# UCENGSOC_BadgeCore.net
KiCad netlist of a schematic drawn in EAGLE
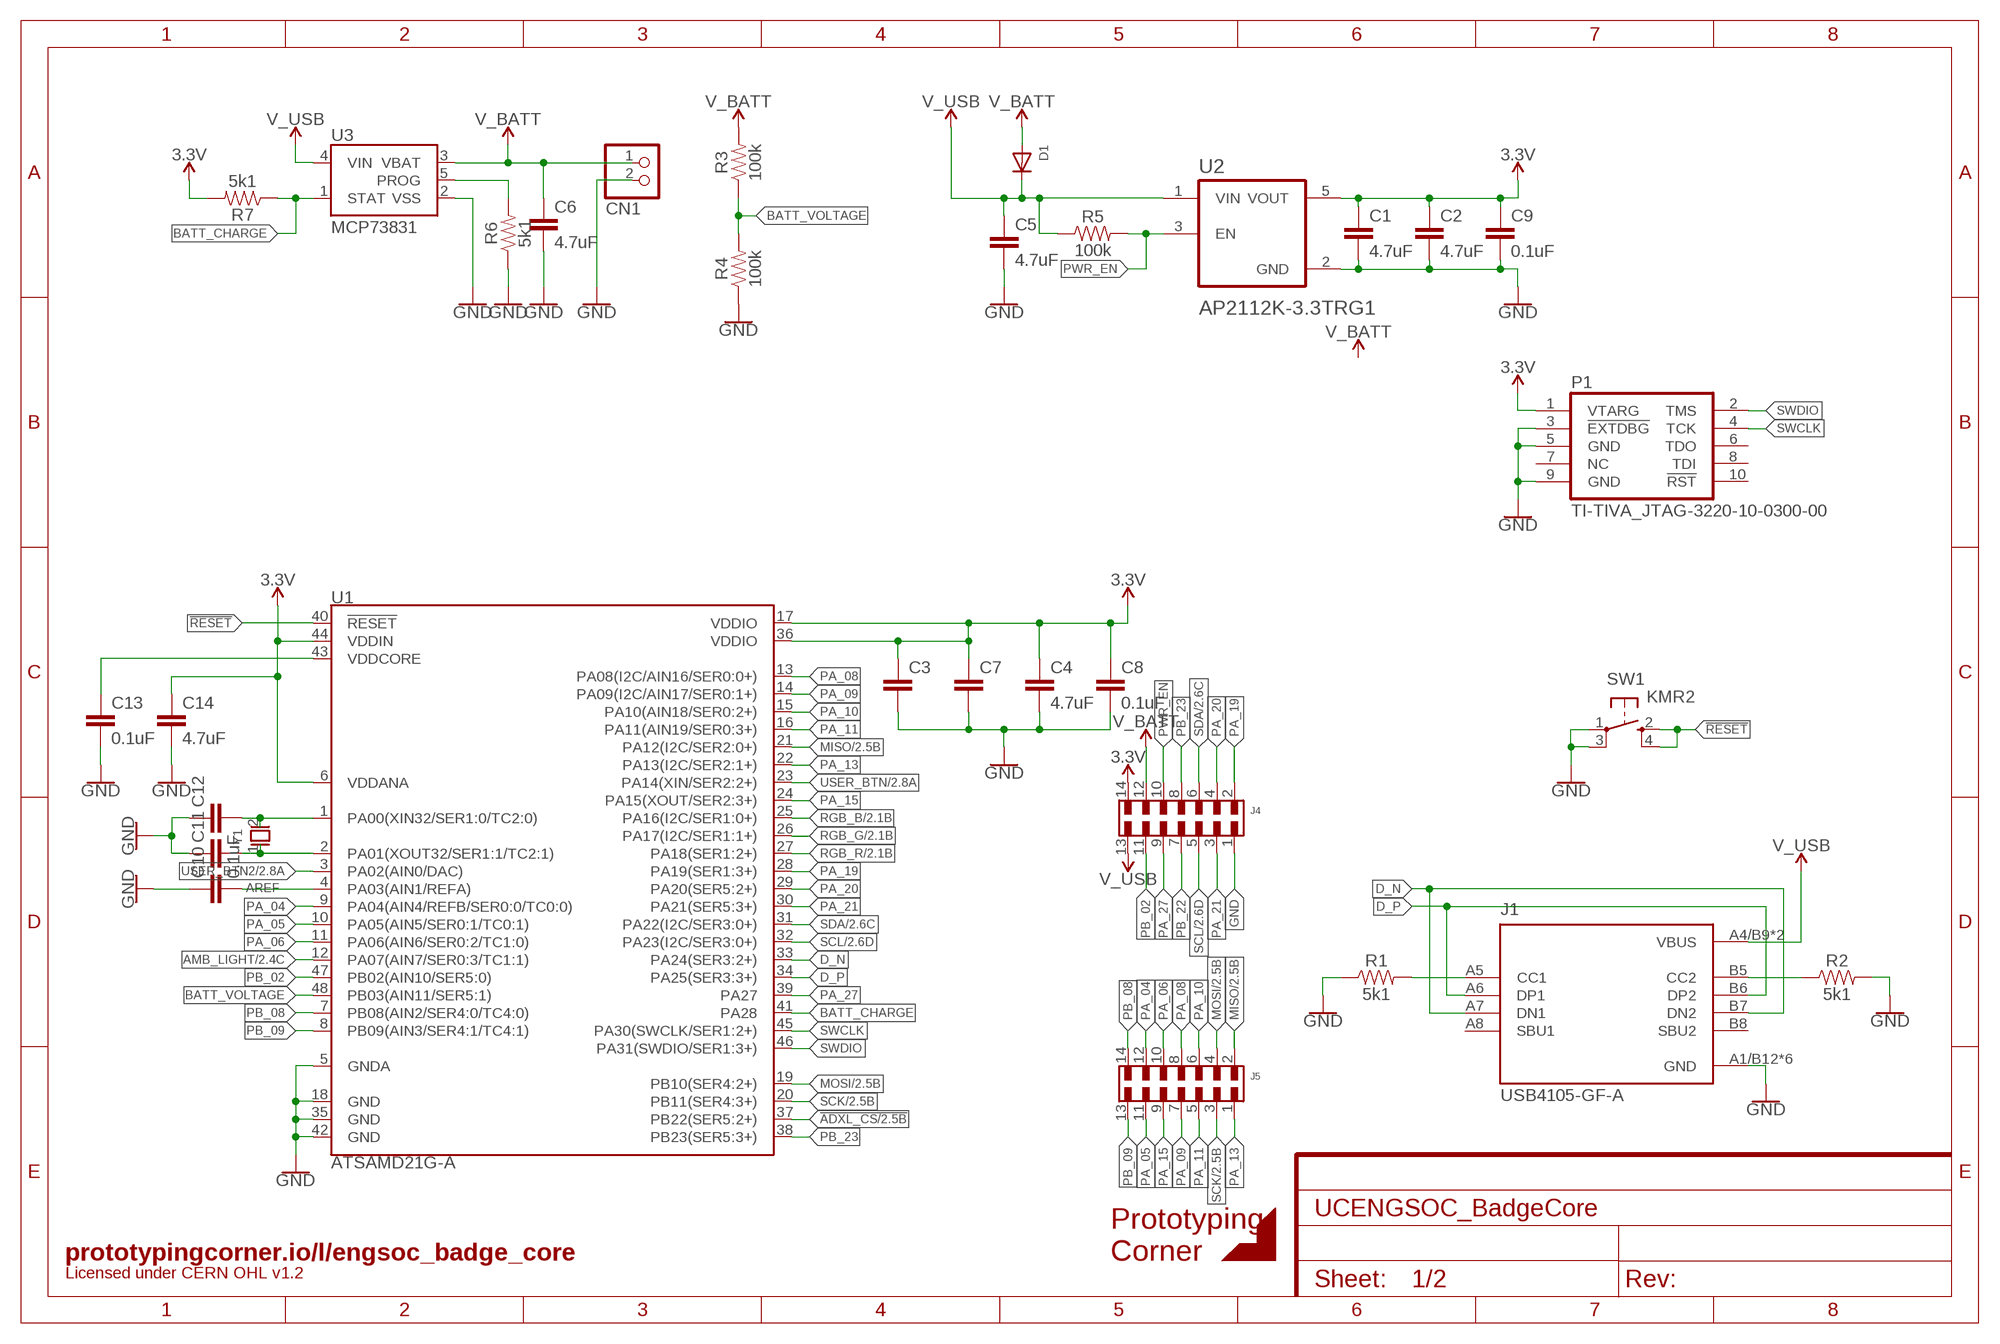
[diagram p0: schematic, sheet 1]
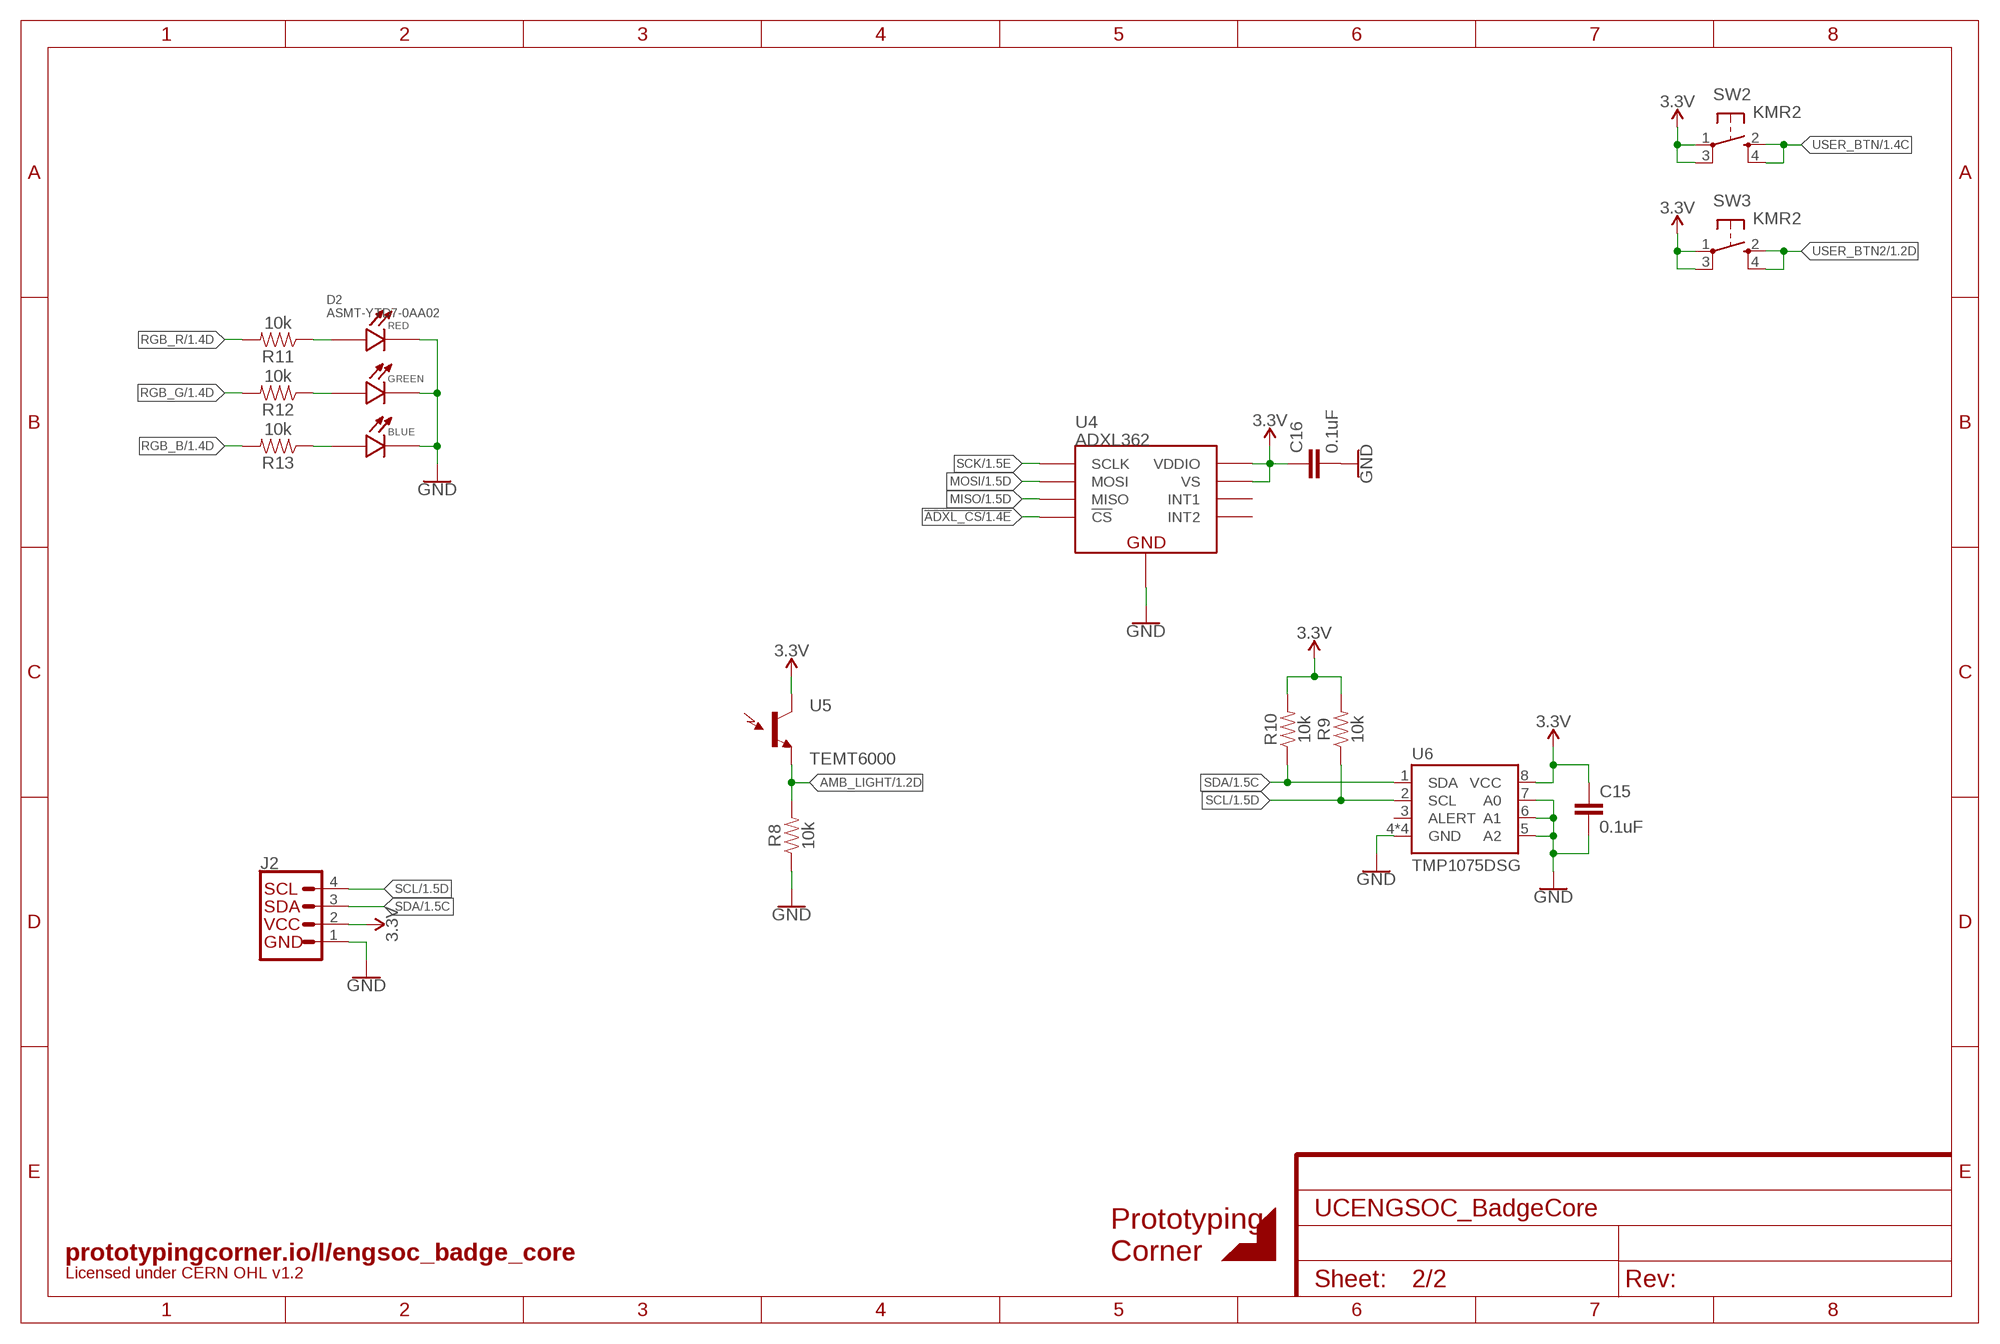
[diagram p1: schematic, sheet 2]

(export (version "E")
  (design (tool "Eeschema 10.0.6"))
  (components
    (comp (ref "C1")
      (value "4.7uF")
      (footprint "eagle-import:1206")
      (libsource (lib "eagle-import") (part "4.7UF-1206-16V-(+80/-20%)"))
    )
    (comp (ref "C2")
      (value "4.7uF")
      (footprint "eagle-import:1206")
      (libsource (lib "eagle-import") (part "4.7UF-1206-16V-(+80/-20%)"))
    )
    (comp (ref "C3")
      (value "4.7UF-1206-16V-(+80/-20%)")
      (footprint "eagle-import:1206")
      (libsource (lib "eagle-import") (part "4.7UF-1206-16V-(+80/-20%)"))
    )
    (comp (ref "C4")
      (value "4.7uF")
      (footprint "eagle-import:1206")
      (libsource (lib "eagle-import") (part "4.7UF-1206-16V-(+80/-20%)"))
    )
    (comp (ref "C5")
      (value "4.7uF")
      (footprint "eagle-import:1206")
      (libsource (lib "eagle-import") (part "4.7UF-1206-16V-(+80/-20%)"))
    )
    (comp (ref "C6")
      (value "4.7uF")
      (footprint "eagle-import:1206")
      (libsource (lib "eagle-import") (part "4.7UF-1206-16V-(+80/-20%)"))
    )
    (comp (ref "C7")
      (value "0.1UF-0603-25V-5%")
      (footprint "eagle-import:0603")
      (libsource (lib "eagle-import") (part "SparkFun-Capacitors_510_0.1UF-0603-25V-5%"))
    )
    (comp (ref "C8")
      (value "0.1uF")
      (footprint "eagle-import:0603")
      (libsource (lib "eagle-import") (part "SparkFun-Capacitors_510_0.1UF-0603-25V-5%"))
    )
    (comp (ref "C9")
      (value "0.1uF")
      (footprint "eagle-import:0603")
      (libsource (lib "eagle-import") (part "SparkFun-Capacitors_510_0.1UF-0603-25V-5%"))
    )
    (comp (ref "C10")
      (value "0.1uF")
      (footprint "eagle-import:0603")
      (libsource (lib "eagle-import") (part "SparkFun-Capacitors_510_0.1UF-0603-25V-5%"))
    )
    (comp (ref "C11")
      (value "15PF-0603-50V-5%")
      (footprint "eagle-import:0603")
      (libsource (lib "eagle-import") (part "15PF-0603-50V-5%"))
    )
    (comp (ref "C12")
      (value "15PF-0603-50V-5%")
      (footprint "eagle-import:0603")
      (libsource (lib "eagle-import") (part "15PF-0603-50V-5%"))
    )
    (comp (ref "C13")
      (value "0.1uF")
      (footprint "eagle-import:0603")
      (libsource (lib "eagle-import") (part "SparkFun-Capacitors_510_0.1UF-0603-25V-5%"))
    )
    (comp (ref "C14")
      (value "4.7uF")
      (footprint "eagle-import:1206")
      (libsource (lib "eagle-import") (part "4.7UF-1206-16V-(+80/-20%)"))
    )
    (comp (ref "CN1")
      (value "JST_2PIN-SMT-RA")
      (footprint "eagle-import:JST-PH-2-SMT-RA")
      (libsource (lib "eagle-import") (part "JST_2PIN-SMT-RA"))
    )
    (comp (ref "D1")
      (value "DIODE_SOD-123FL")
      (footprint "eagle-import:SOD-123FL")
      (libsource (lib "eagle-import") (part "DIODE_SOD-123FL"))
    )
    (comp (ref "J1")
      (value "USB4105-GF-A")
      (footprint "eagle-import:GCT_USB4105-GF-A")
      (fields (field (name "MF") "GCT"))
      (libsource (lib "eagle-import") (part "USB4105-GF-A"))
    )
    (comp (ref "J4")
      (value "6100XX21121_61001421121")
      (footprint "eagle-import:61001421121")
      (libsource (lib "eagle-import") (part "6100XX21121_61001421121"))
    )
    (comp (ref "J5")
      (value "6100XX21121_61001421121")
      (footprint "eagle-import:61001421121")
      (libsource (lib "eagle-import") (part "6100XX21121_61001421121"))
    )
    (comp (ref "P1")
      (value "TI-TIVA_JTAG-3220-10-0300-00")
      (footprint "eagle-import:TI-TIVA_3220-10-0300-00")
      (libsource (lib "eagle-import") (part "TI-TIVA_JTAG-3220-10-0300-00"))
    )
    (comp (ref "R1")
      (value "5k1")
      (footprint "eagle-import:0603")
      (libsource (lib "eagle-import") (part "RESISTOR0603"))
    )
    (comp (ref "R2")
      (value "5k1")
      (footprint "eagle-import:0603")
      (libsource (lib "eagle-import") (part "RESISTOR0603"))
    )
    (comp (ref "R3")
      (value "100k")
      (footprint "eagle-import:0603")
      (libsource (lib "eagle-import") (part "RESISTOR0603"))
    )
    (comp (ref "R4")
      (value "100k")
      (footprint "eagle-import:0603")
      (libsource (lib "eagle-import") (part "RESISTOR0603"))
    )
    (comp (ref "R5")
      (value "100k")
      (footprint "eagle-import:0603")
      (libsource (lib "eagle-import") (part "RESISTOR0603"))
    )
    (comp (ref "R6")
      (value "5k1")
      (footprint "eagle-import:0603")
      (libsource (lib "eagle-import") (part "RESISTOR0603"))
    )
    (comp (ref "R7")
      (value "5k1")
      (footprint "eagle-import:0603")
      (libsource (lib "eagle-import") (part "RESISTOR0603"))
    )
    (comp (ref "SW1")
      (value "KMR2")
      (footprint "eagle-import:KMR2")
      (libsource (lib "eagle-import") (part "SPST_TACT-KMR2"))
    )
    (comp (ref "U$1")
      (value "LOGOSMALL_COPPER")
      (footprint "eagle-import:LOGO_SMALL_COPPER")
      (libsource (lib "eagle-import") (part "LOGOSMALL_COPPER"))
    )
    (comp (ref "U1")
      (value "ATSAMD21G-A")
      (footprint "eagle-import:TQFP-48")
      (libsource (lib "eagle-import") (part "ATSAMD21G-A"))
    )
    (comp (ref "U2")
      (value "AP2112K-3.3TRG1")
      (footprint "eagle-import:SOT95P285X140-5N")
      (fields
        (field (name "DIGI-KEY_PART_NUMBER") "AP2112K-3.3TRG1DICT-ND")
        (field (name "MF") "Diodes Inc.")
      )
      (libsource (lib "eagle-import") (part "AP2112K-3.3TRG1"))
    )
    (comp (ref "U3")
      (value "MCP73831")
      (footprint "eagle-import:SOT23-5")
      (libsource (lib "eagle-import") (part "MCP73831"))
    )
    (comp (ref "Y1")
      (value "FC-135_32.7680KA-A0")
      (footprint "eagle-import:XTAL_FC-135_32.7680KA-A0")
      (fields
        (field (name "DIGI-KEY_PART_NUMBER") "SER4077CT-ND")
        (field (name "MF") "EPSON")
        (field (name "MP") "FC-135 32.7680KA-A0")
      )
      (libsource (lib "eagle-import") (part "FC-135_32.7680KA-A0"))
    )
    (comp (ref "C15")
      (value "0.1uF")
      (footprint "eagle-import:0603")
      (libsource (lib "eagle-import") (part "0.1UF-0603-25V-(+80/-20%)"))
    )
    (comp (ref "C16")
      (value "0.1uF")
      (footprint "eagle-import:0603")
      (libsource (lib "eagle-import") (part "0.1UF-0603-25V-(+80/-20%)"))
    )
    (comp (ref "D2")
      (value "ASMT-YTD7-0AA02")
      (footprint "eagle-import:LED_ASMT-YTD7-0AA02")
      (fields (field (name "MF") "Broadcom Limited"))
      (libsource (lib "eagle-import") (part "ASMT-YTD7-0AA02"))
    )
    (comp (ref "J2")
      (value "QWIIC_CONNECTORJS-1MM")
      (footprint "eagle-import:1X04_1MM_RA")
      (libsource (lib "eagle-import") (part "QWIIC_CONNECTORJS-1MM"))
    )
    (comp (ref "R8")
      (value "10k")
      (footprint "eagle-import:0603")
      (libsource (lib "eagle-import") (part "10KOHM-0603-1/10W-1%"))
    )
    (comp (ref "R9")
      (value "10k")
      (footprint "eagle-import:0603")
      (libsource (lib "eagle-import") (part "10KOHM-0603-1/10W-1%"))
    )
    (comp (ref "R10")
      (value "10k")
      (footprint "eagle-import:0603")
      (libsource (lib "eagle-import") (part "10KOHM-0603-1/10W-1%"))
    )
    (comp (ref "R11")
      (value "10k")
      (footprint "eagle-import:0603")
      (libsource (lib "eagle-import") (part "10KOHM-0603-1/10W-1%"))
    )
    (comp (ref "R12")
      (value "10k")
      (footprint "eagle-import:0603")
      (libsource (lib "eagle-import") (part "10KOHM-0603-1/10W-1%"))
    )
    (comp (ref "R13")
      (value "10k")
      (footprint "eagle-import:0603")
      (libsource (lib "eagle-import") (part "10KOHM-0603-1/10W-1%"))
    )
    (comp (ref "SW2")
      (value "KMR2")
      (footprint "eagle-import:KMR2")
      (libsource (lib "eagle-import") (part "SPST_TACT-KMR2"))
    )
    (comp (ref "SW3")
      (value "KMR2")
      (footprint "eagle-import:KMR2")
      (libsource (lib "eagle-import") (part "SPST_TACT-KMR2"))
    )
    (comp (ref "U$2")
      (value "LOGOSMALL_COPPER")
      (footprint "eagle-import:LOGO_SMALL_COPPER")
      (libsource (lib "eagle-import") (part "LOGOSMALL_COPPER"))
    )
    (comp (ref "U4")
      (value "ADXL362")
      (footprint "eagle-import:ADXL362")
      (libsource (lib "eagle-import") (part "ADXL362"))
    )
    (comp (ref "U5")
      (value "TEMT6000")
      (footprint "eagle-import:TEMT6000-SEN")
      (libsource (lib "eagle-import") (part "TEMT6000"))
    )
    (comp (ref "U6")
      (value "TMP1075DSG")
      (footprint "eagle-import:WSON8")
      (libsource (lib "eagle-import") (part "TMP1075DSG"))
    )
  )
  (nets
    (net (code "1") (name "3.3V") (class "Default")
      (node (ref "C1") (pin "1") (pinfunction "1_1") (pintype "passive"))
      (node (ref "C14") (pin "1") (pinfunction "1_1") (pintype "passive"))
      (node (ref "C15") (pin "1") (pinfunction "1_1") (pintype "passive"))
      (node (ref "C16") (pin "1") (pinfunction "1_1") (pintype "passive"))
      (node (ref "C2") (pin "1") (pinfunction "1_1") (pintype "passive"))
      (node (ref "C3") (pin "1") (pinfunction "1_1") (pintype "passive"))
      (node (ref "C4") (pin "1") (pinfunction "1_1") (pintype "passive"))
      (node (ref "C7") (pin "1") (pinfunction "1_1") (pintype "passive"))
      (node (ref "C8") (pin "1") (pinfunction "1_1") (pintype "passive"))
      (node (ref "C9") (pin "1") (pinfunction "1_1") (pintype "passive"))
      (node (ref "J2") (pin "2") (pinfunction "VCC_2") (pintype "power_in"))
      (node (ref "J4") (pin "14") (pinfunction "14_14") (pintype "passive"))
      (node (ref "P1") (pin "1") (pinfunction "VTARG_1") (pintype "bidirectional"))
      (node (ref "R10") (pin "2") (pinfunction "2_2") (pintype "passive"))
      (node (ref "R7") (pin "2") (pinfunction "2_2") (pintype "passive"))
      (node (ref "R9") (pin "2") (pinfunction "2_2") (pintype "passive"))
      (node (ref "SW2") (pin "1") (pinfunction "P_1") (pintype "passive"))
      (node (ref "SW2") (pin "3") (pinfunction "P1_3") (pintype "passive"))
      (node (ref "SW3") (pin "1") (pinfunction "P_1") (pintype "passive"))
      (node (ref "SW3") (pin "3") (pinfunction "P1_3") (pintype "passive"))
      (node (ref "U1") (pin "17") (pinfunction "VDDIO_17") (pintype "bidirectional"))
      (node (ref "U1") (pin "36") (pinfunction "VDDIO_36") (pintype "bidirectional"))
      (node (ref "U1") (pin "44") (pinfunction "VDDIN_44") (pintype "bidirectional"))
      (node (ref "U1") (pin "6") (pinfunction "VDDANA_6") (pintype "bidirectional"))
      (node (ref "U2") (pin "5") (pinfunction "VOUT_5") (pintype "power_in"))
      (node (ref "U4") (pin "P$1") (pinfunction "VDDIO_P$1") (pintype "bidirectional"))
      (node (ref "U4") (pin "P$14") (pinfunction "VS_P$14") (pintype "bidirectional"))
      (node (ref "U5") (pin "COLLECTOR") (pinfunction "C1_COLLECTOR") (pintype "passive"))
      (node (ref "U6") (pin "8") (pinfunction "VCC_8") (pintype "bidirectional"))
    )
    (net (code "2") (name "AMB_LIGHT") (class "Default")
      (node (ref "R8") (pin "2") (pinfunction "2_2") (pintype "passive"))
      (node (ref "U1") (pin "12") (pinfunction "PA07(AIN7/SER0:3/TC1:1)_12") (pintype "bidirectional"))
      (node (ref "U5") (pin "EMITTER") (pinfunction "E1_EMITTER") (pintype "passive"))
    )
    (net (code "3") (name "AREF") (class "Default")
      (node (ref "C10") (pin "2") (pinfunction "2_2") (pintype "passive"))
      (node (ref "U1") (pin "4") (pinfunction "PA03(AIN1/REFA)_4") (pintype "bidirectional"))
    )
    (net (code "4") (name "BATT_CHARGE") (class "Default")
      (node (ref "R7") (pin "1") (pinfunction "1_1") (pintype "passive"))
      (node (ref "U1") (pin "41") (pinfunction "PA28_41") (pintype "bidirectional"))
      (node (ref "U3") (pin "1") (pinfunction "STAT_1") (pintype "output"))
    )
    (net (code "5") (name "BATT_VOLTAGE") (class "Default")
      (node (ref "R3") (pin "1") (pinfunction "1_1") (pintype "passive"))
      (node (ref "R4") (pin "2") (pinfunction "2_2") (pintype "passive"))
      (node (ref "U1") (pin "48") (pinfunction "PB03(AIN11/SER5:1)_48") (pintype "bidirectional"))
    )
    (net (code "6") (name "D_N") (class "Default")
      (node (ref "J1") (pin "A7") (pinfunction "DN1_A7") (pintype "bidirectional"))
      (node (ref "J1") (pin "B7") (pinfunction "DN2_B7") (pintype "bidirectional"))
      (node (ref "U1") (pin "33") (pinfunction "PA24(SER3:2+)_33") (pintype "bidirectional"))
    )
    (net (code "7") (name "D_P") (class "Default")
      (node (ref "J1") (pin "A6") (pinfunction "DP1_A6") (pintype "bidirectional"))
      (node (ref "J1") (pin "B6") (pinfunction "DP2_B6") (pintype "bidirectional"))
      (node (ref "U1") (pin "34") (pinfunction "PA25(SER3:3+)_34") (pintype "bidirectional"))
    )
    (net (code "8") (name "GND") (class "Default")
      (node (ref "C1") (pin "2") (pinfunction "2_2") (pintype "passive"))
      (node (ref "C10") (pin "1") (pinfunction "1_1") (pintype "passive"))
      (node (ref "C11") (pin "1") (pinfunction "1_1") (pintype "passive"))
      (node (ref "C12") (pin "1") (pinfunction "1_1") (pintype "passive"))
      (node (ref "C13") (pin "2") (pinfunction "2_2") (pintype "passive"))
      (node (ref "C14") (pin "2") (pinfunction "2_2") (pintype "passive"))
      (node (ref "C15") (pin "2") (pinfunction "2_2") (pintype "passive"))
      (node (ref "C16") (pin "2") (pinfunction "2_2") (pintype "passive"))
      (node (ref "C2") (pin "2") (pinfunction "2_2") (pintype "passive"))
      (node (ref "C3") (pin "2") (pinfunction "2_2") (pintype "passive"))
      (node (ref "C4") (pin "2") (pinfunction "2_2") (pintype "passive"))
      (node (ref "C5") (pin "2") (pinfunction "2_2") (pintype "passive"))
      (node (ref "C6") (pin "2") (pinfunction "2_2") (pintype "passive"))
      (node (ref "C7") (pin "2") (pinfunction "2_2") (pintype "passive"))
      (node (ref "C8") (pin "2") (pinfunction "2_2") (pintype "passive"))
      (node (ref "C9") (pin "2") (pinfunction "2_2") (pintype "passive"))
      (node (ref "CN1") (pin "2") (pinfunction "1_2") (pintype "passive"))
      (node (ref "D2") (pin "1") (pinfunction "B_C_1") (pintype "passive"))
      (node (ref "D2") (pin "2") (pinfunction "G_C_2") (pintype "passive"))
      (node (ref "D2") (pin "3") (pinfunction "R_C_3") (pintype "passive"))
      (node (ref "J1") (pin "A1/B12") (pinfunction "GND_A1/B12") (pintype "power_in"))
      (node (ref "J1") (pin "B1/A12") (pinfunction "GND_B1/A12") (pintype "power_in"))
      (node (ref "J1") (pin "G1") (pinfunction "GND_G1") (pintype "power_in"))
      (node (ref "J1") (pin "G2") (pinfunction "GND_G2") (pintype "power_in"))
      (node (ref "J1") (pin "G3") (pinfunction "GND_G3") (pintype "power_in"))
      (node (ref "J1") (pin "G4") (pinfunction "GND_G4") (pintype "power_in"))
      (node (ref "J2") (pin "1") (pinfunction "GND_1") (pintype "power_in"))
      (node (ref "J4") (pin "1") (pinfunction "1_1") (pintype "passive"))
      (node (ref "P1") (pin "3") (pinfunction "~{EXTDBG}_3") (pintype "bidirectional"))
      (node (ref "P1") (pin "5") (pinfunction "GND_5") (pintype "bidirectional"))
      (node (ref "P1") (pin "9") (pinfunction "GND_9") (pintype "bidirectional"))
      (node (ref "R1") (pin "1") (pinfunction "1_1") (pintype "passive"))
      (node (ref "R2") (pin "2") (pinfunction "2_2") (pintype "passive"))
      (node (ref "R4") (pin "1") (pinfunction "1_1") (pintype "passive"))
      (node (ref "R6") (pin "1") (pinfunction "1_1") (pintype "passive"))
      (node (ref "R8") (pin "1") (pinfunction "1_1") (pintype "passive"))
      (node (ref "SW1") (pin "1") (pinfunction "P_1") (pintype "passive"))
      (node (ref "SW1") (pin "3") (pinfunction "P1_3") (pintype "passive"))
      (node (ref "U1") (pin "18") (pinfunction "GND_18") (pintype "bidirectional"))
      (node (ref "U1") (pin "35") (pinfunction "GND_35") (pintype "bidirectional"))
      (node (ref "U1") (pin "42") (pinfunction "GND_42") (pintype "bidirectional"))
      (node (ref "U1") (pin "5") (pinfunction "GNDA_5") (pintype "bidirectional"))
      (node (ref "U2") (pin "2") (pinfunction "GND_2") (pintype "power_in"))
      (node (ref "U3") (pin "2") (pinfunction "VSS_2") (pintype "power_in"))
      (node (ref "U4") (pin "P$12") (pinfunction "GND_P$12") (pintype "bidirectional"))
      (node (ref "U4") (pin "P$13") (pinfunction "GND_P$13") (pintype "bidirectional"))
      (node (ref "U4") (pin "P$16") (pinfunction "GND_P$16") (pintype "bidirectional"))
      (node (ref "U6") (pin "10") (pinfunction "GND_10") (pintype "bidirectional"))
      (node (ref "U6") (pin "11") (pinfunction "GND_11") (pintype "bidirectional"))
      (node (ref "U6") (pin "4") (pinfunction "GND_4") (pintype "bidirectional"))
      (node (ref "U6") (pin "5") (pinfunction "A2_5") (pintype "bidirectional"))
      (node (ref "U6") (pin "6") (pinfunction "A1_6") (pintype "bidirectional"))
      (node (ref "U6") (pin "7") (pinfunction "A0_7") (pintype "bidirectional"))
      (node (ref "U6") (pin "9") (pinfunction "GND_9") (pintype "bidirectional"))
    )
    (net (code "9") (name "MISO") (class "Default")
      (node (ref "J5") (pin "2") (pinfunction "2_2") (pintype "passive"))
      (node (ref "U1") (pin "21") (pinfunction "PA12(I2C/SER2:0+)_21") (pintype "bidirectional"))
      (node (ref "U4") (pin "P$7") (pinfunction "MISO_P$7") (pintype "bidirectional"))
    )
    (net (code "10") (name "MOSI") (class "Default")
      (node (ref "J5") (pin "4") (pinfunction "4_4") (pintype "passive"))
      (node (ref "U1") (pin "19") (pinfunction "PB10(SER4:2+)_19") (pintype "bidirectional"))
      (node (ref "U4") (pin "P$6") (pinfunction "MOSI_P$6") (pintype "bidirectional"))
    )
    (net (code "11") (name "Net-(D2-B_A)") (class "Default")
      (node (ref "D2") (pin "6") (pinfunction "B_A_6") (pintype "passive"))
      (node (ref "R13") (pin "1") (pinfunction "1_1") (pintype "passive"))
    )
    (net (code "12") (name "Net-(D2-G_A)") (class "Default")
      (node (ref "D2") (pin "5") (pinfunction "G_A_5") (pintype "passive"))
      (node (ref "R12") (pin "1") (pinfunction "1_1") (pintype "passive"))
    )
    (net (code "13") (name "Net-(D2-R_A)") (class "Default")
      (node (ref "D2") (pin "4") (pinfunction "R_A_4") (pintype "passive"))
      (node (ref "R11") (pin "1") (pinfunction "1_1") (pintype "passive"))
    )
    (net (code "14") (name "Net-(J1-CC1)") (class "Default")
      (node (ref "J1") (pin "A5") (pinfunction "CC1_A5") (pintype "bidirectional"))
      (node (ref "R1") (pin "2") (pinfunction "2_2") (pintype "passive"))
    )
    (net (code "15") (name "Net-(J1-CC2)") (class "Default")
      (node (ref "J1") (pin "B5") (pinfunction "CC2_B5") (pintype "bidirectional"))
      (node (ref "R2") (pin "1") (pinfunction "1_1") (pintype "passive"))
    )
    (net (code "16") (name "Net-(U1-PA00(XIN32{slash}SER1:0{slash}TC2:0))") (class "Default")
      (node (ref "C12") (pin "2") (pinfunction "2_2") (pintype "passive"))
      (node (ref "U1") (pin "1") (pinfunction "PA00(XIN32/SER1:0/TC2:0)_1") (pintype "bidirectional"))
      (node (ref "Y1") (pin "2") (pinfunction "2_2") (pintype "passive"))
    )
    (net (code "17") (name "Net-(U1-PA01(XOUT32{slash}SER1:1{slash}TC2:1))") (class "Default")
      (node (ref "C11") (pin "2") (pinfunction "2_2") (pintype "passive"))
      (node (ref "U1") (pin "2") (pinfunction "PA01(XOUT32/SER1:1/TC2:1)_2") (pintype "bidirectional"))
      (node (ref "Y1") (pin "1") (pinfunction "1_1") (pintype "passive"))
    )
    (net (code "18") (name "Net-(U1-VDDCORE)") (class "Default")
      (node (ref "C13") (pin "1") (pinfunction "1_1") (pintype "passive"))
      (node (ref "U1") (pin "43") (pinfunction "VDDCORE_43") (pintype "bidirectional"))
    )
    (net (code "19") (name "Net-(U3-PROG)") (class "Default")
      (node (ref "R6") (pin "2") (pinfunction "2_2") (pintype "passive"))
      (node (ref "U3") (pin "5") (pinfunction "PROG_5") (pintype "input"))
    )
    (net (code "20") (name "PA_04") (class "Default")
      (node (ref "J5") (pin "12") (pinfunction "12_12") (pintype "passive"))
      (node (ref "U1") (pin "9") (pinfunction "PA04(AIN4/REFB/SER0:0/TC0:0)_9") (pintype "bidirectional"))
    )
    (net (code "21") (name "PA_05") (class "Default")
      (node (ref "J5") (pin "11") (pinfunction "11_11") (pintype "passive"))
      (node (ref "U1") (pin "10") (pinfunction "PA05(AIN5/SER0:1/TC0:1)_10") (pintype "bidirectional"))
    )
    (net (code "22") (name "PA_06") (class "Default")
      (node (ref "J5") (pin "10") (pinfunction "10_10") (pintype "passive"))
      (node (ref "U1") (pin "11") (pinfunction "PA06(AIN6/SER0:2/TC1:0)_11") (pintype "bidirectional"))
    )
    (net (code "23") (name "PA_08") (class "Default")
      (node (ref "J5") (pin "8") (pinfunction "8_8") (pintype "passive"))
      (node (ref "U1") (pin "13") (pinfunction "PA08(I2C/AIN16/SER0:0+)_13") (pintype "bidirectional"))
    )
    (net (code "24") (name "PA_09") (class "Default")
      (node (ref "J5") (pin "7") (pinfunction "7_7") (pintype "passive"))
      (node (ref "U1") (pin "14") (pinfunction "PA09(I2C/AIN17/SER0:1+)_14") (pintype "bidirectional"))
    )
    (net (code "25") (name "PA_10") (class "Default")
      (node (ref "J5") (pin "6") (pinfunction "6_6") (pintype "passive"))
      (node (ref "U1") (pin "15") (pinfunction "PA10(AIN18/SER0:2+)_15") (pintype "bidirectional"))
    )
    (net (code "26") (name "PA_11") (class "Default")
      (node (ref "J5") (pin "5") (pinfunction "5_5") (pintype "passive"))
      (node (ref "U1") (pin "16") (pinfunction "PA11(AIN19/SER0:3+)_16") (pintype "bidirectional"))
    )
    (net (code "27") (name "PA_13") (class "Default")
      (node (ref "J5") (pin "1") (pinfunction "1_1") (pintype "passive"))
      (node (ref "U1") (pin "22") (pinfunction "PA13(I2C/SER2:1+)_22") (pintype "bidirectional"))
    )
    (net (code "28") (name "PA_15") (class "Default")
      (node (ref "J5") (pin "9") (pinfunction "9_9") (pintype "passive"))
      (node (ref "U1") (pin "24") (pinfunction "PA15(XOUT/SER2:3+)_24") (pintype "bidirectional"))
    )
    (net (code "29") (name "PA_19") (class "Default")
      (node (ref "J4") (pin "2") (pinfunction "2_2") (pintype "passive"))
      (node (ref "U1") (pin "28") (pinfunction "PA19(SER1:3+)_28") (pintype "bidirectional"))
    )
    (net (code "30") (name "PA_20") (class "Default")
      (node (ref "J4") (pin "4") (pinfunction "4_4") (pintype "passive"))
      (node (ref "U1") (pin "29") (pinfunction "PA20(SER5:2+)_29") (pintype "bidirectional"))
    )
    (net (code "31") (name "PA_21") (class "Default")
      (node (ref "J4") (pin "3") (pinfunction "3_3") (pintype "passive"))
      (node (ref "U1") (pin "30") (pinfunction "PA21(SER5:3+)_30") (pintype "bidirectional"))
    )
    (net (code "32") (name "PA_27") (class "Default")
      (node (ref "J4") (pin "9") (pinfunction "9_9") (pintype "passive"))
      (node (ref "U1") (pin "39") (pinfunction "PA27_39") (pintype "bidirectional"))
    )
    (net (code "33") (name "PB_02") (class "Default")
      (node (ref "J4") (pin "11") (pinfunction "11_11") (pintype "passive"))
      (node (ref "U1") (pin "47") (pinfunction "PB02(AIN10/SER5:0)_47") (pintype "bidirectional"))
    )
    (net (code "34") (name "PB_08") (class "Default")
      (node (ref "J5") (pin "14") (pinfunction "14_14") (pintype "passive"))
      (node (ref "U1") (pin "7") (pinfunction "PB08(AIN2/SER4:0/TC4:0)_7") (pintype "bidirectional"))
    )
    (net (code "35") (name "PB_09") (class "Default")
      (node (ref "J5") (pin "13") (pinfunction "13_13") (pintype "passive"))
      (node (ref "U1") (pin "8") (pinfunction "PB09(AIN3/SER4:1/TC4:1)_8") (pintype "bidirectional"))
    )
    (net (code "36") (name "PB_22") (class "Default")
      (node (ref "J4") (pin "7") (pinfunction "7_7") (pintype "passive"))
    )
    (net (code "37") (name "PB_23") (class "Default")
      (node (ref "J4") (pin "8") (pinfunction "8_8") (pintype "passive"))
      (node (ref "U1") (pin "38") (pinfunction "PB23(SER5:3+)_38") (pintype "bidirectional"))
    )
    (net (code "38") (name "PWR_EN") (class "Default")
      (node (ref "J4") (pin "10") (pinfunction "10_10") (pintype "passive"))
      (node (ref "R5") (pin "2") (pinfunction "2_2") (pintype "passive"))
      (node (ref "U2") (pin "3") (pinfunction "EN_3") (pintype "input"))
    )
    (net (code "39") (name "RGB_B") (class "Default")
      (node (ref "R13") (pin "2") (pinfunction "2_2") (pintype "passive"))
      (node (ref "U1") (pin "25") (pinfunction "PA16(I2C/SER1:0+)_25") (pintype "bidirectional"))
    )
    (net (code "40") (name "RGB_G") (class "Default")
      (node (ref "R12") (pin "2") (pinfunction "2_2") (pintype "passive"))
      (node (ref "U1") (pin "26") (pinfunction "PA17(I2C/SER1:1+)_26") (pintype "bidirectional"))
    )
    (net (code "41") (name "RGB_R") (class "Default")
      (node (ref "R11") (pin "2") (pinfunction "2_2") (pintype "passive"))
      (node (ref "U1") (pin "27") (pinfunction "PA18(SER1:2+)_27") (pintype "bidirectional"))
    )
    (net (code "42") (name "SCK") (class "Default")
      (node (ref "J5") (pin "3") (pinfunction "3_3") (pintype "passive"))
      (node (ref "U1") (pin "20") (pinfunction "PB11(SER4:3+)_20") (pintype "bidirectional"))
      (node (ref "U4") (pin "P$4") (pinfunction "SCLK_P$4") (pintype "bidirectional"))
    )
    (net (code "43") (name "SCL") (class "Default")
      (node (ref "J2") (pin "4") (pinfunction "SCL_4") (pintype "passive"))
      (node (ref "J4") (pin "5") (pinfunction "5_5") (pintype "passive"))
      (node (ref "R9") (pin "1") (pinfunction "1_1") (pintype "passive"))
      (node (ref "U1") (pin "32") (pinfunction "PA23(I2C/SER3:0+)_32") (pintype "bidirectional"))
      (node (ref "U6") (pin "2") (pinfunction "SCL_2") (pintype "bidirectional"))
    )
    (net (code "44") (name "SDA") (class "Default")
      (node (ref "J2") (pin "3") (pinfunction "SDA_3") (pintype "passive"))
      (node (ref "J4") (pin "6") (pinfunction "6_6") (pintype "passive"))
      (node (ref "R10") (pin "1") (pinfunction "1_1") (pintype "passive"))
      (node (ref "U1") (pin "31") (pinfunction "PA22(I2C/SER3:0+)_31") (pintype "bidirectional"))
      (node (ref "U6") (pin "1") (pinfunction "SDA_1") (pintype "bidirectional"))
    )
    (net (code "45") (name "SWCLK") (class "Default")
      (node (ref "P1") (pin "4") (pinfunction "TCK_4") (pintype "bidirectional"))
      (node (ref "U1") (pin "45") (pinfunction "PA30(SWCLK/SER1:2+)_45") (pintype "bidirectional"))
    )
    (net (code "46") (name "SWDIO") (class "Default")
      (node (ref "P1") (pin "2") (pinfunction "TMS_2") (pintype "bidirectional"))
      (node (ref "U1") (pin "46") (pinfunction "PA31(SWDIO/SER1:3+)_46") (pintype "bidirectional"))
    )
    (net (code "47") (name "USER_BTN") (class "Default")
      (node (ref "SW2") (pin "2") (pinfunction "S_2") (pintype "passive"))
      (node (ref "SW2") (pin "4") (pinfunction "S1_4") (pintype "passive"))
      (node (ref "U1") (pin "23") (pinfunction "PA14(XIN/SER2:2+)_23") (pintype "bidirectional"))
    )
    (net (code "48") (name "USER_BTN2") (class "Default")
      (node (ref "SW3") (pin "2") (pinfunction "S_2") (pintype "passive"))
      (node (ref "SW3") (pin "4") (pinfunction "S1_4") (pintype "passive"))
      (node (ref "U1") (pin "3") (pinfunction "PA02(AIN0/DAC)_3") (pintype "bidirectional"))
    )
    (net (code "49") (name "V_BATT") (class "Default")
      (node (ref "C6") (pin "1") (pinfunction "1_1") (pintype "passive"))
      (node (ref "CN1") (pin "1") (pinfunction "2_1") (pintype "passive"))
      (node (ref "D1") (pin "A") (pinfunction "A_A") (pintype "passive"))
      (node (ref "J4") (pin "12") (pinfunction "12_12") (pintype "passive"))
      (node (ref "R3") (pin "2") (pinfunction "2_2") (pintype "passive"))
      (node (ref "U3") (pin "3") (pinfunction "VBAT_3") (pintype "power_in"))
    )
    (net (code "50") (name "V_USB") (class "Default")
      (node (ref "C5") (pin "1") (pinfunction "1_1") (pintype "passive"))
      (node (ref "D1") (pin "C") (pinfunction "C_C") (pintype "passive"))
      (node (ref "J1") (pin "A4/B9") (pinfunction "VBUS_A4/B9") (pintype "power_in"))
      (node (ref "J1") (pin "B4/A9") (pinfunction "VBUS_B4/A9") (pintype "power_in"))
      (node (ref "J4") (pin "13") (pinfunction "13_13") (pintype "passive"))
      (node (ref "R5") (pin "1") (pinfunction "1_1") (pintype "passive"))
      (node (ref "U2") (pin "1") (pinfunction "VIN_1") (pintype "power_in"))
      (node (ref "U3") (pin "4") (pinfunction "VIN_4") (pintype "power_in"))
    )
    (net (code "51") (name "unconnected-(J1-SBU1-PadA8)") (class "Default")
      (node (ref "J1") (pin "A8") (pinfunction "SBU1_A8") (pintype "bidirectional"))
    )
    (net (code "52") (name "unconnected-(J1-SBU2-PadB8)") (class "Default")
      (node (ref "J1") (pin "B8") (pinfunction "SBU2_B8") (pintype "bidirectional"))
    )
    (net (code "53") (name "unconnected-(P1-NC-Pad7)") (class "Default")
      (node (ref "P1") (pin "7") (pinfunction "NC_7") (pintype "bidirectional"))
    )
    (net (code "54") (name "unconnected-(P1-TDI-Pad8)") (class "Default")
      (node (ref "P1") (pin "8") (pinfunction "TDI_8") (pintype "bidirectional"))
    )
    (net (code "55") (name "unconnected-(P1-TDO-Pad6)") (class "Default")
      (node (ref "P1") (pin "6") (pinfunction "TDO_6") (pintype "bidirectional"))
    )
    (net (code "56") (name "unconnected-(P1-~{RST}-Pad10)") (class "Default")
      (node (ref "P1") (pin "10") (pinfunction "~{RST}_10") (pintype "bidirectional"))
    )
    (net (code "57") (name "unconnected-(U4-INT1-PadP$11)") (class "Default")
      (node (ref "U4") (pin "P$11") (pinfunction "INT1_P$11") (pintype "bidirectional"))
    )
    (net (code "58") (name "unconnected-(U4-INT2-PadP$9)") (class "Default")
      (node (ref "U4") (pin "P$9") (pinfunction "INT2_P$9") (pintype "bidirectional"))
    )
    (net (code "59") (name "unconnected-(U6-ALERT-Pad3)") (class "Default")
      (node (ref "U6") (pin "3") (pinfunction "ALERT_3") (pintype "bidirectional"))
    )
    (net (code "60") (name "~{ADXL_CS}") (class "Default")
      (node (ref "U1") (pin "37") (pinfunction "PB22(SER5:2+)_37") (pintype "bidirectional"))
      (node (ref "U4") (pin "P$8") (pinfunction "~{CS}_P$8") (pintype "bidirectional"))
    )
    (net (code "61") (name "~{RESET}") (class "Default")
      (node (ref "SW1") (pin "2") (pinfunction "S_2") (pintype "passive"))
      (node (ref "SW1") (pin "4") (pinfunction "S1_4") (pintype "passive"))
      (node (ref "U1") (pin "40") (pinfunction "~{RESET}_40") (pintype "bidirectional"))
    )
  )
)
